# io.net
KiCad netlist of a schematic drawn in Altium Designer
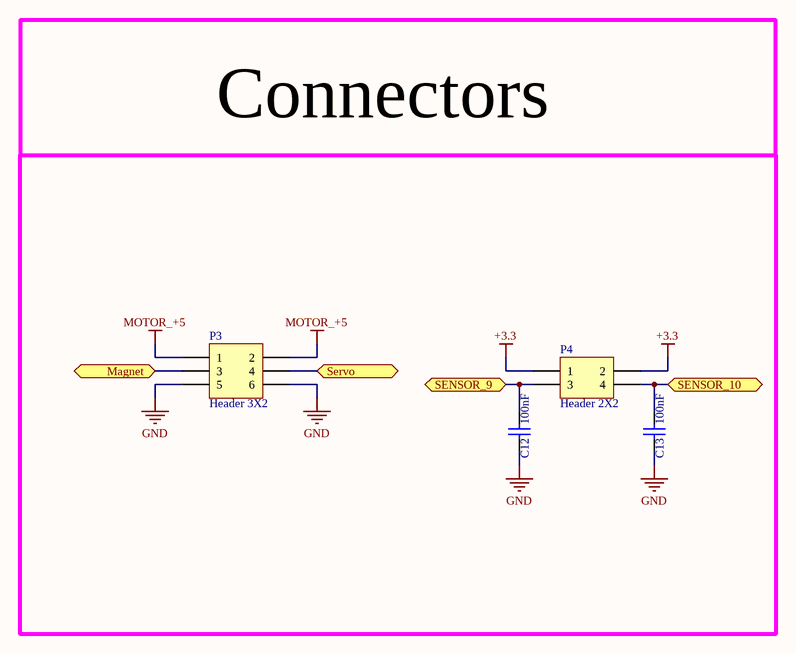
[diagram p0: io.SchDoc]

(export (version "E")
  (design (tool "Eeschema 10.0.6"))
  (components
    (comp (ref "C12")
      (value "100nF")
      (footprint "CAP_0402i_1005m -N")
      (description "capacitor")
      (libsource (lib "IDSC std generic parts") (part "Cap"))
    )
    (comp (ref "C13")
      (value "100nF")
      (footprint "CAP_0402i_1005m -N")
      (description "capacitor")
      (libsource (lib "IDSC std generic parts") (part "Cap"))
    )
    (comp (ref "P3")
      (value "Header 3X2")
      (footprint "HDR2X3")
      (description "Header, 3-Pin, Dual row")
      (libsource (lib "IDSC std connectors") (part "Header 3X2"))
    )
    (comp (ref "P4")
      (value "Header 2X2")
      (footprint "HDR2X2")
      (description "Header, 2-Pin, Dual row")
      (libsource (lib "IDSC std connectors") (part "Header 2X2"))
    )
  )
  (nets
    (net (code "1") (name "+3.3") (class "Default")
      (node (ref "P4") (pin "1") (pinfunction "1_1") (pintype "passive"))
      (node (ref "P4") (pin "2") (pinfunction "2_2") (pintype "passive"))
    )
    (net (code "2") (name "/Magnet") (class "Default")
      (node (ref "P3") (pin "3") (pinfunction "3_3") (pintype "passive"))
    )
    (net (code "3") (name "/SENSOR_9") (class "Default")
      (node (ref "C12") (pin "2") (pinfunction "2_2") (pintype "passive"))
      (node (ref "P4") (pin "3") (pinfunction "3_3") (pintype "passive"))
    )
    (net (code "4") (name "/SENSOR_10") (class "Default")
      (node (ref "C13") (pin "2") (pinfunction "2_2") (pintype "passive"))
      (node (ref "P4") (pin "4") (pinfunction "4_4") (pintype "passive"))
    )
    (net (code "5") (name "/Servo") (class "Default")
      (node (ref "P3") (pin "4") (pinfunction "4_4") (pintype "passive"))
    )
    (net (code "6") (name "GND") (class "Default")
      (node (ref "C12") (pin "1") (pinfunction "1_1") (pintype "passive"))
      (node (ref "C13") (pin "1") (pinfunction "1_1") (pintype "passive"))
      (node (ref "P3") (pin "5") (pinfunction "5_5") (pintype "passive"))
      (node (ref "P3") (pin "6") (pinfunction "6_6") (pintype "passive"))
    )
    (net (code "7") (name "MOTOR_+5") (class "Default")
      (node (ref "P3") (pin "1") (pinfunction "1_1") (pintype "passive"))
      (node (ref "P3") (pin "2") (pinfunction "2_2") (pintype "passive"))
    )
  )
)
